# SCH_N20__2022-09-17.net
KiCad netlist of a schematic drawn in EasyEDA
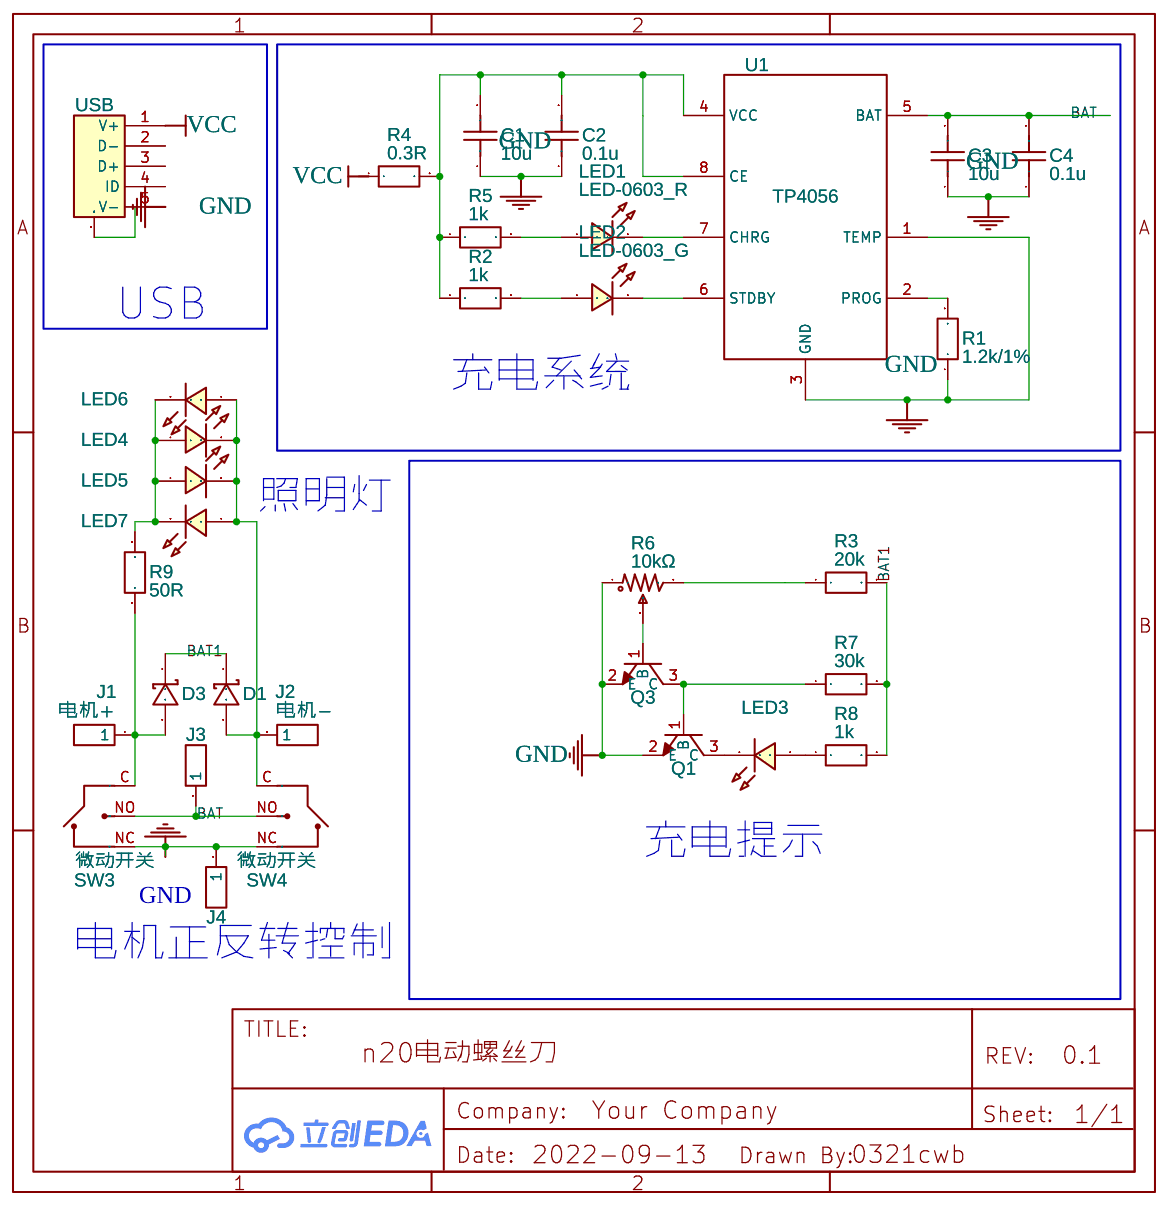
[diagram p0: schematic sheet]

(export (version "E")
  (design (tool "Eeschema 10.0.6"))
  (components
    (comp (ref "C1") (value "10u") (libsource (lib "") (part "C_0603_US")))
    (comp (ref "C2") (value "0.1u") (libsource (lib "") (part "C_0603_US")))
    (comp (ref "C3") (value "10u") (libsource (lib "") (part "C_0603_US")))
    (comp (ref "C4") (value "0.1u") (libsource (lib "") (part "C_0603_US")))
    (comp (ref "D1")
      (value "1N5817WS")
      (fields (field (name "BOM_Supplier Part") "C489146"))
      (libsource (lib "") (part "1N5817WS"))
    )
    (comp (ref "D3")
      (value "1N5817WS")
      (fields (field (name "BOM_Supplier Part") "C489146"))
      (libsource (lib "") (part "1N5817WS"))
    )
    (comp (ref "J1")
      (value "电机+")
      (fields (field (name "BOM_Supplier Part") "C81276"))
      (libsource (lib "") (part "HDR-M-2.54_1x1_1"))
    )
    (comp (ref "J2")
      (value "电机-")
      (fields (field (name "BOM_Supplier Part") "C81276"))
      (libsource (lib "") (part "HDR-M-2.54_1x1_2"))
    )
    (comp (ref "J3")
      (value "HDR-M-2.54_1x1")
      (fields (field (name "BOM_Supplier Part") "C81276"))
      (libsource (lib "") (part "HDR-M-2.54_1x1_3"))
    )
    (comp (ref "J4")
      (value "HDR-M-2.54_1x1")
      (fields (field (name "BOM_Supplier Part") "C81276"))
      (libsource (lib "") (part "HDR-M-2.54_1x1"))
    )
    (comp (ref "LED1")
      (value "LED-0603_R")
      (fields
        (field (name "BOM_Manufacturer Part") "19-217/R6C-AL1M2VY/3T")
        (field (name "BOM_Supplier Part") "C72044")
      )
      (libsource (lib "") (part "LED-0603_R_1"))
    )
    (comp (ref "LED2")
      (value "LED-0603_G")
      (fields
        (field (name "BOM_Manufacturer Part") "19-217/GHC-YR1S2/3T")
        (field (name "BOM_Supplier Part") "C72043")
      )
      (libsource (lib "") (part "LED-0603_G"))
    )
    (comp (ref "LED3")
      (value "LED-0603_R")
      (fields
        (field (name "BOM_Manufacturer Part") "19-217/R6C-AL1M2VY/3T")
        (field (name "BOM_Supplier Part") "C72044")
      )
      (libsource (lib "") (part "LED-0603_R"))
    )
    (comp (ref "LED4")
      (value "LED-0603_R")
      (fields
        (field (name "BOM_Manufacturer Part") "19-217/R6C-AL1M2VY/3T")
        (field (name "BOM_Supplier Part") "C72044")
      )
      (libsource (lib "") (part "LED-0603_R_1"))
    )
    (comp (ref "LED5")
      (value "LED-0603_R")
      (fields
        (field (name "BOM_Manufacturer Part") "19-217/R6C-AL1M2VY/3T")
        (field (name "BOM_Supplier Part") "C72044")
      )
      (libsource (lib "") (part "LED-0603_R_1"))
    )
    (comp (ref "LED6")
      (value "LED-0603_R")
      (fields
        (field (name "BOM_Manufacturer Part") "19-217/R6C-AL1M2VY/3T")
        (field (name "BOM_Supplier Part") "C72044")
      )
      (libsource (lib "") (part "LED-0603_R"))
    )
    (comp (ref "LED7")
      (value "LED-0603_R")
      (fields
        (field (name "BOM_Manufacturer Part") "19-217/R6C-AL1M2VY/3T")
        (field (name "BOM_Supplier Part") "C72044")
      )
      (libsource (lib "") (part "LED-0603_R"))
    )
    (comp (ref "Q1")
      (value "S8050_C2926165")
      (fields (field (name "BOM_Manufacturer Part") "S8050") (field (name "BOM_Supplier Part") "C2926165"))
      (libsource (lib "") (part "S8050_C2926165"))
    )
    (comp (ref "Q3")
      (value "S8050_C2926165")
      (fields (field (name "BOM_Manufacturer Part") "S8050") (field (name "BOM_Supplier Part") "C2926165"))
      (libsource (lib "") (part "S8050_C2926165"))
    )
    (comp (ref "R1") (value "1.2k/1%") (libsource (lib "") (part "R_0603_EU_1")))
    (comp (ref "R2") (value "1k") (libsource (lib "") (part "R_0603_EU")))
    (comp (ref "R3") (value "20k") (libsource (lib "") (part "R_0603_EU")))
    (comp (ref "R4") (value "0.3R") (libsource (lib "") (part "R_0603_EU")))
    (comp (ref "R5") (value "1k") (libsource (lib "") (part "R_0603_EU")))
    (comp (ref "R6")
      (value "10kΩ")
      (fields
        (field (name "BOM_Manufacturer Part") "TC33X-2-103E")
        (field (name "BOM_Supplier Part") "C719176")
      )
      (libsource (lib "") (part "TC33X-2-103E"))
    )
    (comp (ref "R7") (value "30k") (libsource (lib "") (part "R_0603_EU")))
    (comp (ref "R8") (value "1k") (libsource (lib "") (part "R_0603_EU")))
    (comp (ref "R9") (value "50R") (libsource (lib "") (part "R_0603_EU_1")))
    (comp (ref "SW3")
      (value "微动开关")
      (fields (field (name "BOM_Manufacturer Part") "LF-108") (field (name "BOM_Supplier Part") "C2914466"))
      (libsource (lib "") (part "LF-108_1"))
    )
    (comp (ref "SW4")
      (value "微动开关")
      (fields (field (name "BOM_Manufacturer Part") "LF-108") (field (name "BOM_Supplier Part") "C2914466"))
      (libsource (lib "") (part "LF-108"))
    )
    (comp (ref "U1") (value "TP4056") (libsource (lib "") (part "Unknown_310_-200")))
    (comp (ref "USB")
      (value "micro 5PFour-legged board7.2There is a column card point0.4m")
      (fields (field (name "BOM_Supplier Part") "C40943"))
      (libsource (lib "") (part "micro 5PFour-legged board7.2There is a column card point0.4m"))
    )
  )
  (nets
    (net (code "1") (name "/BAT") (class "Default")
      (node (ref "C3") (pin "2") (pinfunction "2_2") (pintype "unspecified"))
      (node (ref "C4") (pin "2") (pinfunction "2_2") (pintype "unspecified"))
      (node (ref "J3") (pin "1") (pinfunction "1_1") (pintype "input"))
      (node (ref "SW3") (pin "NO") (pinfunction "NO_NO") (pintype "unspecified"))
      (node (ref "SW4") (pin "NO") (pinfunction "NO_NO") (pintype "unspecified"))
      (node (ref "U1") (pin "5") (pinfunction "BAT_5") (pintype "unspecified"))
    )
    (net (code "2") (name "/BAT1") (class "Default")
      (node (ref "D1") (pin "1") (pinfunction "1_1") (pintype "unspecified"))
      (node (ref "D3") (pin "1") (pinfunction "1_1") (pintype "unspecified"))
      (node (ref "R3") (pin "2") (pinfunction "2_2") (pintype "unspecified"))
      (node (ref "R7") (pin "2") (pinfunction "2_2") (pintype "unspecified"))
      (node (ref "R8") (pin "2") (pinfunction "2_2") (pintype "unspecified"))
    )
    (net (code "3") (name "GND") (class "Default")
      (node (ref "C1") (pin "1") (pinfunction "1_1") (pintype "unspecified"))
      (node (ref "C2") (pin "1") (pinfunction "1_1") (pintype "unspecified"))
      (node (ref "C3") (pin "1") (pinfunction "1_1") (pintype "unspecified"))
      (node (ref "C4") (pin "1") (pinfunction "1_1") (pintype "unspecified"))
      (node (ref "J4") (pin "1") (pinfunction "1_1") (pintype "input"))
      (node (ref "Q1") (pin "2") (pinfunction "E_2") (pintype "input"))
      (node (ref "Q3") (pin "2") (pinfunction "E_2") (pintype "input"))
      (node (ref "R1") (pin "1") (pinfunction "1_1") (pintype "unspecified"))
      (node (ref "R6") (pin "1") (pinfunction "1_1") (pintype "unspecified"))
      (node (ref "SW3") (pin "NC") (pinfunction "NC_NC") (pintype "unspecified"))
      (node (ref "SW4") (pin "NC") (pinfunction "NC_NC") (pintype "unspecified"))
      (node (ref "U1") (pin "1") (pinfunction "TEMP_1") (pintype "unspecified"))
      (node (ref "U1") (pin "3") (pinfunction "GND_3") (pintype "unspecified"))
      (node (ref "USB") (pin "5") (pinfunction "V-_5") (pintype "unspecified"))
    )
    (net (code "4") (name "Net-(D1-Pad2)") (class "Default")
      (node (ref "D1") (pin "2") (pinfunction "2_2") (pintype "unspecified"))
      (node (ref "J2") (pin "1") (pinfunction "1_1") (pintype "input"))
      (node (ref "LED4") (pin "2") (pinfunction "2_2") (pintype "unspecified"))
      (node (ref "LED5") (pin "2") (pinfunction "2_2") (pintype "unspecified"))
      (node (ref "LED6") (pin "1") (pinfunction "1_1") (pintype "unspecified"))
      (node (ref "LED7") (pin "1") (pinfunction "1_1") (pintype "unspecified"))
      (node (ref "SW4") (pin "C") (pinfunction "C_C") (pintype "unspecified"))
    )
    (net (code "5") (name "Net-(D3-Pad2)") (class "Default")
      (node (ref "D3") (pin "2") (pinfunction "2_2") (pintype "unspecified"))
      (node (ref "J1") (pin "1") (pinfunction "1_1") (pintype "input"))
      (node (ref "R9") (pin "1") (pinfunction "1_1") (pintype "unspecified"))
      (node (ref "SW3") (pin "C") (pinfunction "C_C") (pintype "unspecified"))
    )
    (net (code "6") (name "Net-(LED1-Pad1)") (class "Default")
      (node (ref "LED1") (pin "1") (pinfunction "1_1") (pintype "unspecified"))
      (node (ref "R5") (pin "2") (pinfunction "2_2") (pintype "unspecified"))
    )
    (net (code "7") (name "Net-(LED2-Pad1)") (class "Default")
      (node (ref "LED2") (pin "1") (pinfunction "1_1") (pintype "unspecified"))
      (node (ref "R2") (pin "2") (pinfunction "2_2") (pintype "unspecified"))
    )
    (net (code "8") (name "Net-(LED3-Pad1)") (class "Default")
      (node (ref "LED3") (pin "1") (pinfunction "1_1") (pintype "unspecified"))
      (node (ref "R8") (pin "1") (pinfunction "1_1") (pintype "unspecified"))
    )
    (net (code "9") (name "Net-(LED4-Pad1)") (class "Default")
      (node (ref "LED4") (pin "1") (pinfunction "1_1") (pintype "unspecified"))
      (node (ref "LED5") (pin "1") (pinfunction "1_1") (pintype "unspecified"))
      (node (ref "LED6") (pin "2") (pinfunction "2_2") (pintype "unspecified"))
      (node (ref "LED7") (pin "2") (pinfunction "2_2") (pintype "unspecified"))
      (node (ref "R9") (pin "2") (pinfunction "2_2") (pintype "unspecified"))
    )
    (net (code "10") (name "Net-(Q1-B)") (class "Default")
      (node (ref "Q1") (pin "1") (pinfunction "B_1") (pintype "input"))
      (node (ref "Q3") (pin "3") (pinfunction "C_3") (pintype "input"))
      (node (ref "R7") (pin "1") (pinfunction "1_1") (pintype "unspecified"))
    )
    (net (code "11") (name "Net-(Q1-C)") (class "Default")
      (node (ref "LED3") (pin "2") (pinfunction "2_2") (pintype "unspecified"))
      (node (ref "Q1") (pin "3") (pinfunction "C_3") (pintype "input"))
    )
    (net (code "12") (name "Net-(Q3-B)") (class "Default")
      (node (ref "Q3") (pin "1") (pinfunction "B_1") (pintype "input"))
      (node (ref "R6") (pin "2") (pinfunction "2_2") (pintype "unspecified"))
    )
    (net (code "13") (name "Net-(R3-Pad1)") (class "Default")
      (node (ref "R3") (pin "1") (pinfunction "1_1") (pintype "unspecified"))
      (node (ref "R6") (pin "3") (pinfunction "3_3") (pintype "unspecified"))
    )
    (net (code "14") (name "Net-(U1-CE)") (class "Default")
      (node (ref "C1") (pin "2") (pinfunction "2_2") (pintype "unspecified"))
      (node (ref "C2") (pin "2") (pinfunction "2_2") (pintype "unspecified"))
      (node (ref "R2") (pin "1") (pinfunction "1_1") (pintype "unspecified"))
      (node (ref "R4") (pin "2") (pinfunction "2_2") (pintype "unspecified"))
      (node (ref "R5") (pin "1") (pinfunction "1_1") (pintype "unspecified"))
      (node (ref "U1") (pin "4") (pinfunction "VCC_4") (pintype "unspecified"))
      (node (ref "U1") (pin "8") (pinfunction "CE_8") (pintype "unspecified"))
    )
    (net (code "15") (name "Net-(U1-CHRG)") (class "Default")
      (node (ref "LED1") (pin "2") (pinfunction "2_2") (pintype "unspecified"))
      (node (ref "U1") (pin "7") (pinfunction "CHRG_7") (pintype "unspecified"))
    )
    (net (code "16") (name "Net-(U1-PROG)") (class "Default")
      (node (ref "R1") (pin "2") (pinfunction "2_2") (pintype "unspecified"))
      (node (ref "U1") (pin "2") (pinfunction "PROG_2") (pintype "unspecified"))
    )
    (net (code "17") (name "Net-(U1-STDBY)") (class "Default")
      (node (ref "LED2") (pin "2") (pinfunction "2_2") (pintype "unspecified"))
      (node (ref "U1") (pin "6") (pinfunction "STDBY_6") (pintype "unspecified"))
    )
    (net (code "18") (name "VCC") (class "Default")
      (node (ref "R4") (pin "1") (pinfunction "1_1") (pintype "unspecified"))
      (node (ref "USB") (pin "1") (pinfunction "V+_1") (pintype "unspecified"))
    )
    (net (code "19") (name "unconnected-(USB-D+-Pad3)") (class "Default")
      (node (ref "USB") (pin "3") (pinfunction "D+_3") (pintype "unspecified"))
    )
    (net (code "20") (name "unconnected-(USB-D--Pad2)") (class "Default")
      (node (ref "USB") (pin "2") (pinfunction "D-_2") (pintype "unspecified"))
    )
    (net (code "21") (name "unconnected-(USB-ID-Pad4)") (class "Default")
      (node (ref "USB") (pin "4") (pinfunction "ID_4") (pintype "unspecified"))
    )
    (net (code "22") (name "unconnected-(USB-MTN6-Pad0)") (class "Default")
      (node (ref "USB") (pin "0") (pinfunction "MTN6_0") (pintype "input"))
    )
  )
)
